# 9DofImu.net
KiCad netlist of a schematic drawn in EAGLE
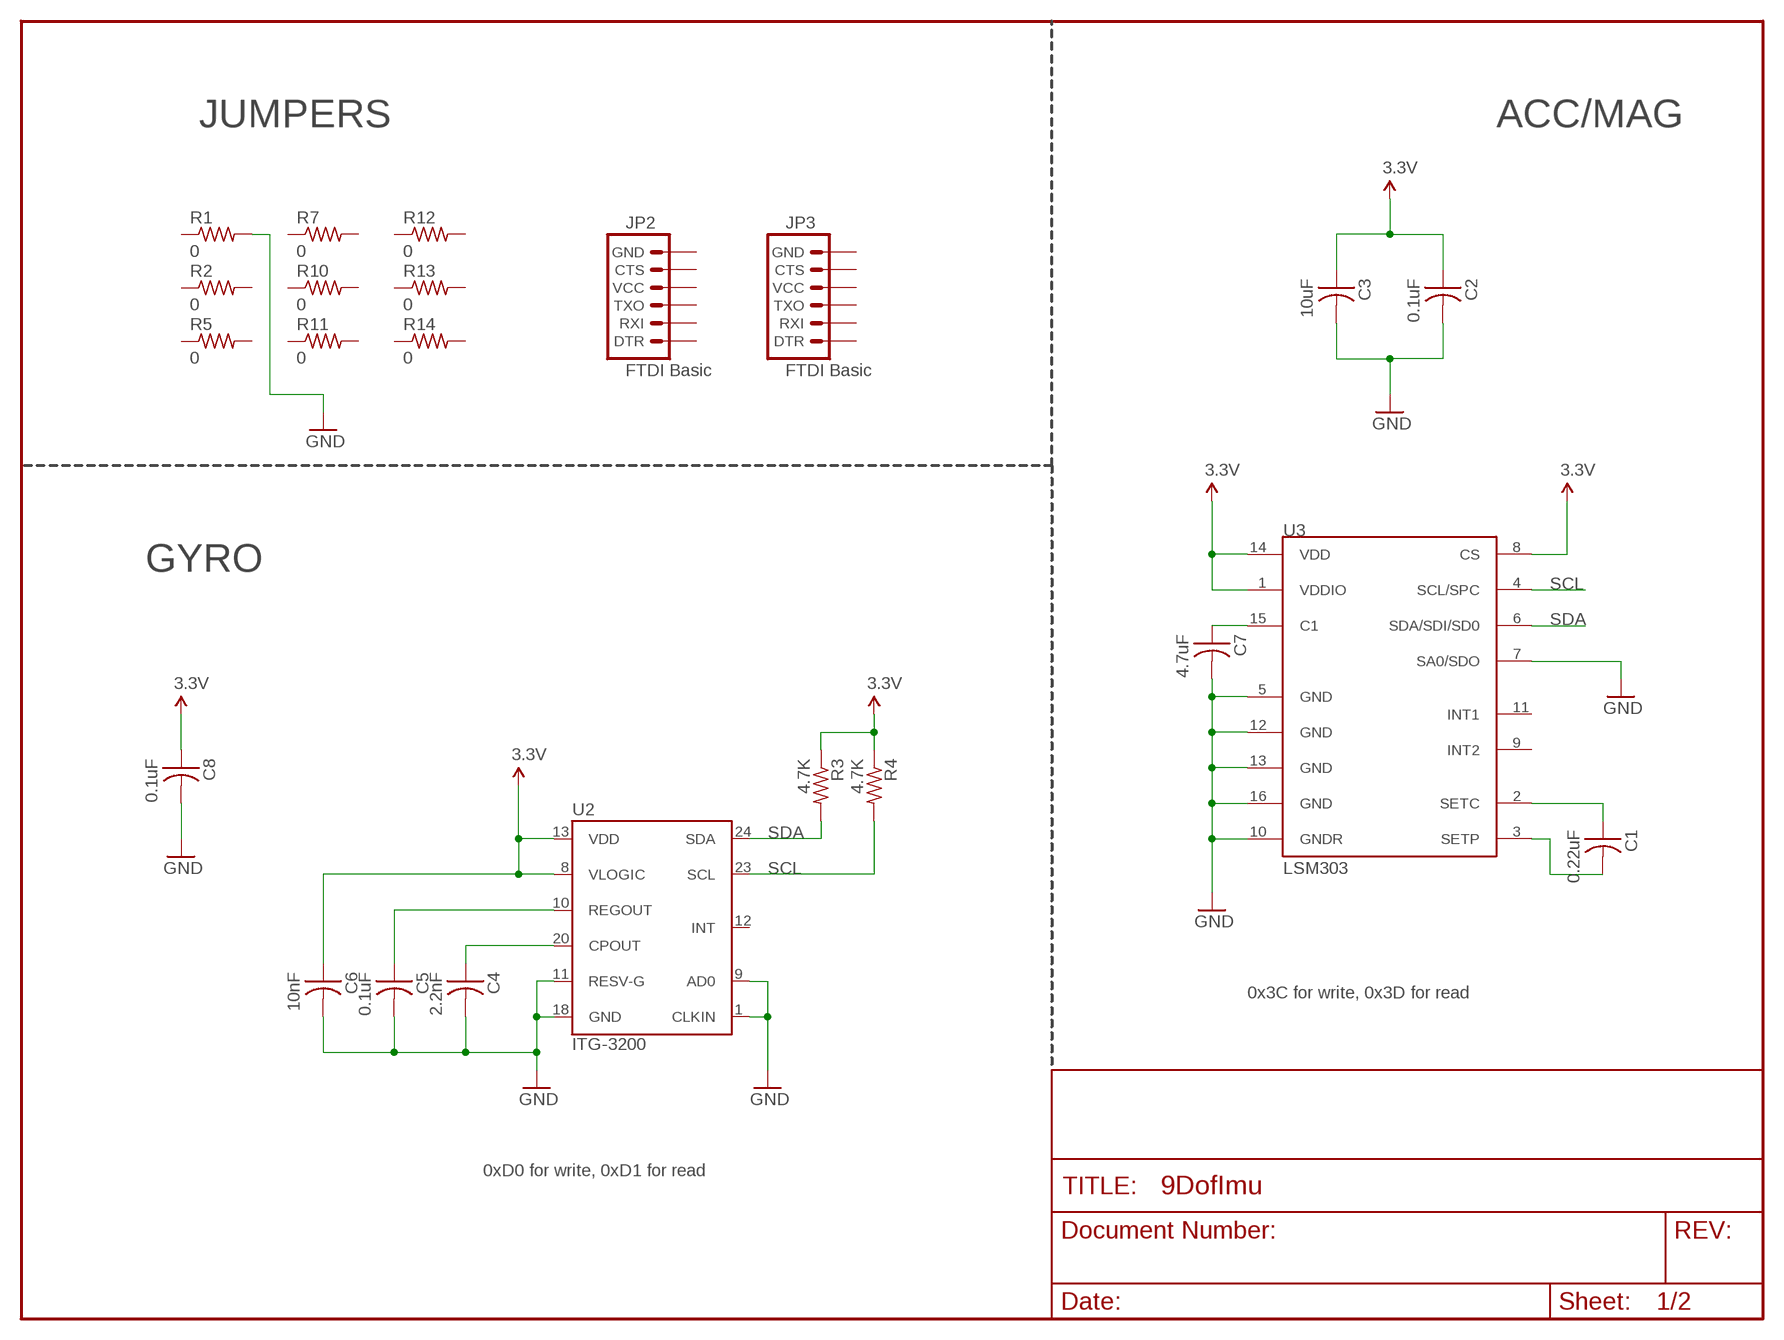
[diagram p0: schematic, sheet 1]
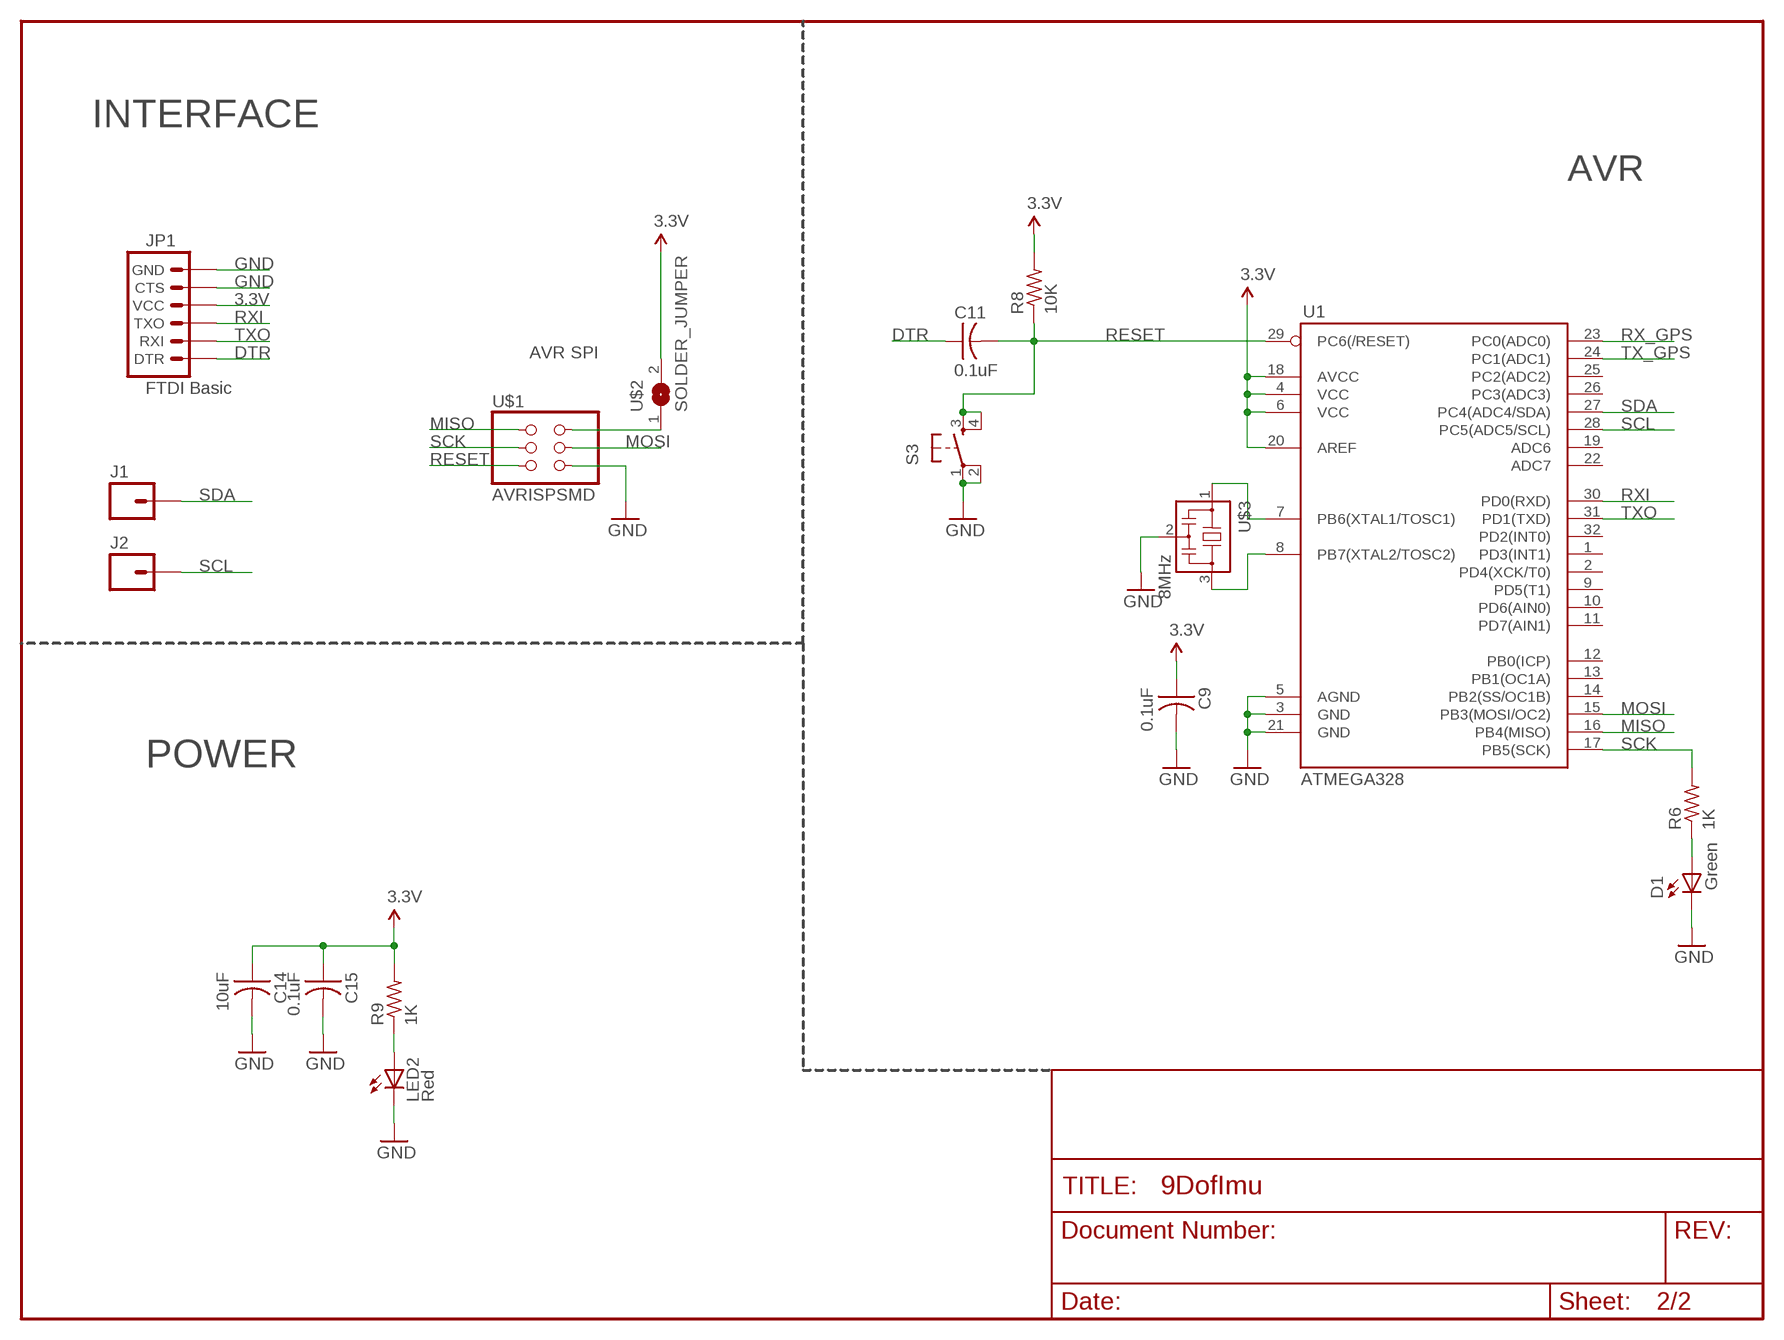
[diagram p1: schematic, sheet 2]

(export (version "E")
  (design (tool "Eeschema 10.0.6"))
  (components
    (comp (ref "C9")
      (value "0.1uF")
      (footprint "eagle-import:C1206")
      (libsource (lib "eagle-import") (part "CAP-US1206"))
    )
    (comp (ref "C11")
      (value "0.1uF")
      (footprint "eagle-import:C1206")
      (libsource (lib "eagle-import") (part "CAP-US1206"))
    )
    (comp (ref "C14")
      (value "10uF")
      (footprint "eagle-import:C1206")
      (libsource (lib "eagle-import") (part "CAP-US1206"))
    )
    (comp (ref "C15")
      (value "0.1uF")
      (footprint "eagle-import:C1206")
      (libsource (lib "eagle-import") (part "CAP-US1206"))
    )
    (comp (ref "D1")
      (value "Green")
      (footprint "eagle-import:LED-1206")
      (libsource (lib "eagle-import") (part "LED1206"))
    )
    (comp (ref "J1")
      (value "M01PTH")
      (footprint "eagle-import:1X01")
      (libsource (lib "eagle-import") (part "M01PTH"))
    )
    (comp (ref "J2")
      (value "M01PTH")
      (footprint "eagle-import:1X01")
      (libsource (lib "eagle-import") (part "M01PTH"))
    )
    (comp (ref "JP1")
      (value "FTDI Basic")
      (footprint "eagle-import:1X06-KIT")
      (libsource (lib "eagle-import") (part "ARDUINO_SERIAL_PROGRAMPTH-KIT"))
    )
    (comp (ref "LED2")
      (value "Red")
      (footprint "eagle-import:LED-1206")
      (libsource (lib "eagle-import") (part "LED1206"))
    )
    (comp (ref "R6")
      (value "1K")
      (footprint "eagle-import:R1206")
      (libsource (lib "eagle-import") (part "RES-US1206"))
    )
    (comp (ref "R8")
      (value "10K")
      (footprint "eagle-import:R1206")
      (libsource (lib "eagle-import") (part "RES-US1206"))
    )
    (comp (ref "R9")
      (value "1K")
      (footprint "eagle-import:R1206FAB")
      (libsource (lib "eagle-import") (part "RES-US1206FAB"))
    )
    (comp (ref "S3")
      (value "6MM_SWITCH6MM_SWITCH")
      (footprint "eagle-import:6MM_SWITCH")
      (libsource (lib "eagle-import") (part "6MM_SWITCH6MM_SWITCH"))
    )
    (comp (ref "U$1")
      (value "AVRISPSMD")
      (footprint "eagle-import:2X03SMD")
      (libsource (lib "eagle-import") (part "AVRISPSMD"))
    )
    (comp (ref "U$2")
      (value "SOLDER_JUMPER")
      (footprint "eagle-import:SJFAB")
      (libsource (lib "eagle-import") (part "SOLDER_JUMPER"))
    )
    (comp (ref "U$3")
      (value "8MHz")
      (footprint "eagle-import:EFOBM")
      (libsource (lib "eagle-import") (part "RESONATOR"))
    )
    (comp (ref "U1")
      (value "ATMEGA328")
      (footprint "eagle-import:TQFP32-08")
      (libsource (lib "eagle-import") (part "ATMEGA168"))
    )
    (comp (ref "C1")
      (value "0.22uF")
      (footprint "eagle-import:C1206")
      (libsource (lib "eagle-import") (part "CAP-US1206"))
    )
    (comp (ref "C2")
      (value "0.1uF")
      (footprint "eagle-import:C1206")
      (libsource (lib "eagle-import") (part "CAP-US1206"))
    )
    (comp (ref "C3")
      (value "10uF")
      (footprint "eagle-import:C1206")
      (libsource (lib "eagle-import") (part "CAP-US1206"))
    )
    (comp (ref "C4")
      (value "2.2nF")
      (footprint "eagle-import:C1206")
      (libsource (lib "eagle-import") (part "CAP-US1206"))
    )
    (comp (ref "C5")
      (value "0.1uF")
      (footprint "eagle-import:C1206")
      (libsource (lib "eagle-import") (part "CAP-US1206"))
    )
    (comp (ref "C6")
      (value "10nF")
      (footprint "eagle-import:C1206")
      (libsource (lib "eagle-import") (part "CAP-US1206"))
    )
    (comp (ref "C7")
      (value "4.7uF")
      (footprint "eagle-import:C1206")
      (libsource (lib "eagle-import") (part "CAP-US1206"))
    )
    (comp (ref "C8")
      (value "0.1uF")
      (footprint "eagle-import:C1206")
      (libsource (lib "eagle-import") (part "CAP-US1206"))
    )
    (comp (ref "JP2")
      (value "FTDI Basic")
      (footprint "eagle-import:1X06-KIT")
      (libsource (lib "eagle-import") (part "ARDUINO_SERIAL_PROGRAMPTH-KIT"))
    )
    (comp (ref "JP3")
      (value "FTDI Basic")
      (footprint "eagle-import:1X06-KIT")
      (libsource (lib "eagle-import") (part "ARDUINO_SERIAL_PROGRAMPTH-KIT"))
    )
    (comp (ref "R1")
      (value "0")
      (footprint "eagle-import:R1206FAB")
      (libsource (lib "eagle-import") (part "RES-US1206FAB"))
    )
    (comp (ref "R2")
      (value "0")
      (footprint "eagle-import:R1206FAB")
      (libsource (lib "eagle-import") (part "RES-US1206FAB"))
    )
    (comp (ref "R3")
      (value "4.7K")
      (footprint "eagle-import:R1206")
      (libsource (lib "eagle-import") (part "RES-US1206"))
    )
    (comp (ref "R4")
      (value "4.7K")
      (footprint "eagle-import:R1206FAB")
      (libsource (lib "eagle-import") (part "RES-US1206FAB"))
    )
    (comp (ref "R5")
      (value "0")
      (footprint "eagle-import:R1206FAB")
      (libsource (lib "eagle-import") (part "RES-US1206FAB"))
    )
    (comp (ref "R7")
      (value "0")
      (footprint "eagle-import:R1206FAB")
      (libsource (lib "eagle-import") (part "RES-US1206FAB"))
    )
    (comp (ref "R10")
      (value "0")
      (footprint "eagle-import:R1206FAB")
      (libsource (lib "eagle-import") (part "RES-US1206FAB"))
    )
    (comp (ref "R11")
      (value "0")
      (footprint "eagle-import:R1206FAB")
      (libsource (lib "eagle-import") (part "RES-US1206FAB"))
    )
    (comp (ref "R12")
      (value "0")
      (footprint "eagle-import:R1206FAB")
      (libsource (lib "eagle-import") (part "RES-US1206FAB"))
    )
    (comp (ref "R13")
      (value "0")
      (footprint "eagle-import:R1206FAB")
      (libsource (lib "eagle-import") (part "RES-US1206FAB"))
    )
    (comp (ref "R14")
      (value "0")
      (footprint "eagle-import:R1206FAB")
      (libsource (lib "eagle-import") (part "RES-US1206FAB"))
    )
    (comp (ref "U2")
      (value "ITG-3200")
      (footprint "eagle-import:QFN-24")
      (libsource (lib "eagle-import") (part "ITG-3200"))
    )
    (comp (ref "U3")
      (value "LSM303")
      (footprint "eagle-import:LGA16-3MM")
      (libsource (lib "eagle-import") (part "LSM303"))
    )
  )
  (nets
    (net (code "1") (name "3.3V") (class "Default")
      (node (ref "C14") (pin "1") (pinfunction "1_1") (pintype "passive"))
      (node (ref "C15") (pin "1") (pinfunction "1_1") (pintype "passive"))
      (node (ref "C2") (pin "1") (pinfunction "1_1") (pintype "passive"))
      (node (ref "C3") (pin "1") (pinfunction "1_1") (pintype "passive"))
      (node (ref "C6") (pin "1") (pinfunction "1_1") (pintype "passive"))
      (node (ref "C8") (pin "1") (pinfunction "1_1") (pintype "passive"))
      (node (ref "C9") (pin "1") (pinfunction "1_1") (pintype "passive"))
      (node (ref "JP1") (pin "4") (pinfunction "VCC_4") (pintype "passive"))
      (node (ref "R3") (pin "1") (pinfunction "1_1") (pintype "passive"))
      (node (ref "R4") (pin "1") (pinfunction "1_1") (pintype "passive"))
      (node (ref "R8") (pin "2") (pinfunction "2_2") (pintype "passive"))
      (node (ref "R9") (pin "2") (pinfunction "2_2") (pintype "passive"))
      (node (ref "U$2") (pin "2") (pinfunction "2_2") (pintype "passive"))
      (node (ref "U1") (pin "18") (pinfunction "AVCC_18") (pintype "bidirectional"))
      (node (ref "U1") (pin "20") (pinfunction "AREF_20") (pintype "bidirectional"))
      (node (ref "U1") (pin "4") (pinfunction "VCC_4") (pintype "bidirectional"))
      (node (ref "U1") (pin "6") (pinfunction "VCC_6") (pintype "bidirectional"))
      (node (ref "U2") (pin "13") (pinfunction "VDD_13") (pintype "bidirectional"))
      (node (ref "U2") (pin "8") (pinfunction "VLOGIC_8") (pintype "bidirectional"))
      (node (ref "U3") (pin "1") (pinfunction "VDDIO_1") (pintype "bidirectional"))
      (node (ref "U3") (pin "14") (pinfunction "VDD_14") (pintype "bidirectional"))
      (node (ref "U3") (pin "8") (pinfunction "CS_8") (pintype "bidirectional"))
    )
    (net (code "2") (name "DTR") (class "Default")
      (node (ref "C11") (pin "1") (pinfunction "1_1") (pintype "passive"))
      (node (ref "JP1") (pin "1") (pinfunction "DTR_1") (pintype "passive"))
    )
    (net (code "3") (name "GND") (class "Default")
      (node (ref "C14") (pin "2") (pinfunction "2_2") (pintype "passive"))
      (node (ref "C15") (pin "2") (pinfunction "2_2") (pintype "passive"))
      (node (ref "C2") (pin "2") (pinfunction "2_2") (pintype "passive"))
      (node (ref "C3") (pin "2") (pinfunction "2_2") (pintype "passive"))
      (node (ref "C4") (pin "2") (pinfunction "2_2") (pintype "passive"))
      (node (ref "C5") (pin "2") (pinfunction "2_2") (pintype "passive"))
      (node (ref "C6") (pin "2") (pinfunction "2_2") (pintype "passive"))
      (node (ref "C7") (pin "2") (pinfunction "2_2") (pintype "passive"))
      (node (ref "C8") (pin "2") (pinfunction "2_2") (pintype "passive"))
      (node (ref "C9") (pin "2") (pinfunction "2_2") (pintype "passive"))
      (node (ref "D1") (pin "C") (pinfunction "C_C") (pintype "passive"))
      (node (ref "JP1") (pin "5") (pinfunction "CTS_5") (pintype "passive"))
      (node (ref "JP1") (pin "6") (pinfunction "GND_6") (pintype "passive"))
      (node (ref "LED2") (pin "C") (pinfunction "C_C") (pintype "passive"))
      (node (ref "R1") (pin "2") (pinfunction "2_2") (pintype "passive"))
      (node (ref "S3") (pin "1") (pinfunction "P_1") (pintype "passive"))
      (node (ref "S3") (pin "2") (pinfunction "P1_2") (pintype "passive"))
      (node (ref "U$1") (pin "6") (pinfunction "GND_6") (pintype "passive"))
      (node (ref "U$3") (pin "2") (pinfunction "2_2") (pintype "passive"))
      (node (ref "U1") (pin "21") (pinfunction "GND_21") (pintype "bidirectional"))
      (node (ref "U1") (pin "3") (pinfunction "GND_3") (pintype "bidirectional"))
      (node (ref "U1") (pin "5") (pinfunction "AGND_5") (pintype "bidirectional"))
      (node (ref "U2") (pin "1") (pinfunction "CLKIN_1") (pintype "bidirectional"))
      (node (ref "U2") (pin "11") (pinfunction "RESV-G_11") (pintype "bidirectional"))
      (node (ref "U2") (pin "18") (pinfunction "GND_18") (pintype "bidirectional"))
      (node (ref "U2") (pin "9") (pinfunction "AD0_9") (pintype "bidirectional"))
      (node (ref "U3") (pin "10") (pinfunction "GNDR_10") (pintype "bidirectional"))
      (node (ref "U3") (pin "12") (pinfunction "GND_12") (pintype "bidirectional"))
      (node (ref "U3") (pin "13") (pinfunction "GND_13") (pintype "bidirectional"))
      (node (ref "U3") (pin "16") (pinfunction "GND_16") (pintype "bidirectional"))
      (node (ref "U3") (pin "5") (pinfunction "GND_5") (pintype "bidirectional"))
      (node (ref "U3") (pin "7") (pinfunction "SA0/SDO_7") (pintype "bidirectional"))
    )
    (net (code "4") (name "MISO") (class "Default")
      (node (ref "U$1") (pin "1") (pinfunction "MISO_1") (pintype "passive"))
      (node (ref "U1") (pin "16") (pinfunction "PB4(MISO)_16") (pintype "bidirectional"))
    )
    (net (code "5") (name "MOSI") (class "Default")
      (node (ref "U$1") (pin "4") (pinfunction "MOSI_4") (pintype "passive"))
      (node (ref "U1") (pin "15") (pinfunction "PB3(MOSI/OC2)_15") (pintype "bidirectional"))
    )
    (net (code "6") (name "Net-(D1-PadA)") (class "Default")
      (node (ref "D1") (pin "A") (pinfunction "A_A") (pintype "passive"))
      (node (ref "R6") (pin "1") (pinfunction "1_1") (pintype "passive"))
    )
    (net (code "7") (name "Net-(LED2-PadA)") (class "Default")
      (node (ref "LED2") (pin "A") (pinfunction "A_A") (pintype "passive"))
      (node (ref "R9") (pin "1") (pinfunction "1_1") (pintype "passive"))
    )
    (net (code "8") (name "Net-(U$1-VCC)") (class "Default")
      (node (ref "U$1") (pin "2") (pinfunction "VCC_2") (pintype "passive"))
      (node (ref "U$2") (pin "1") (pinfunction "1_1") (pintype "passive"))
    )
    (net (code "9") (name "Net-(U1-PB6(XTAL1{slash}TOSC1))") (class "Default")
      (node (ref "U$3") (pin "1") (pinfunction "1_1") (pintype "passive"))
      (node (ref "U1") (pin "7") (pinfunction "PB6(XTAL1/TOSC1)_7") (pintype "bidirectional"))
    )
    (net (code "10") (name "Net-(U1-PB7(XTAL2{slash}TOSC2))") (class "Default")
      (node (ref "U$3") (pin "3") (pinfunction "3_3") (pintype "passive"))
      (node (ref "U1") (pin "8") (pinfunction "PB7(XTAL2/TOSC2)_8") (pintype "bidirectional"))
    )
    (net (code "11") (name "Net-(U2-CPOUT)") (class "Default")
      (node (ref "C4") (pin "1") (pinfunction "1_1") (pintype "passive"))
      (node (ref "U2") (pin "20") (pinfunction "CPOUT_20") (pintype "bidirectional"))
    )
    (net (code "12") (name "Net-(U2-REGOUT)") (class "Default")
      (node (ref "C5") (pin "1") (pinfunction "1_1") (pintype "passive"))
      (node (ref "U2") (pin "10") (pinfunction "REGOUT_10") (pintype "bidirectional"))
    )
    (net (code "13") (name "Net-(U3-C1)") (class "Default")
      (node (ref "C7") (pin "1") (pinfunction "1_1") (pintype "passive"))
      (node (ref "U3") (pin "15") (pinfunction "C1_15") (pintype "bidirectional"))
    )
    (net (code "14") (name "Net-(U3-SETC)") (class "Default")
      (node (ref "C1") (pin "1") (pinfunction "1_1") (pintype "passive"))
      (node (ref "U3") (pin "2") (pinfunction "SETC_2") (pintype "bidirectional"))
    )
    (net (code "15") (name "Net-(U3-SETP)") (class "Default")
      (node (ref "C1") (pin "2") (pinfunction "2_2") (pintype "passive"))
      (node (ref "U3") (pin "3") (pinfunction "SETP_3") (pintype "bidirectional"))
    )
    (net (code "16") (name "RESET") (class "Default")
      (node (ref "C11") (pin "2") (pinfunction "2_2") (pintype "passive"))
      (node (ref "R8") (pin "1") (pinfunction "1_1") (pintype "passive"))
      (node (ref "S3") (pin "3") (pinfunction "S_3") (pintype "passive"))
      (node (ref "S3") (pin "4") (pinfunction "S1_4") (pintype "passive"))
      (node (ref "U$1") (pin "5") (pinfunction "RST_5") (pintype "passive"))
      (node (ref "U1") (pin "29") (pinfunction "PC6(/RESET)_29") (pintype "bidirectional"))
    )
    (net (code "17") (name "RXI") (class "Default")
      (node (ref "JP1") (pin "3") (pinfunction "TXO_3") (pintype "passive"))
      (node (ref "U1") (pin "30") (pinfunction "PD0(RXD)_30") (pintype "bidirectional"))
    )
    (net (code "18") (name "RX_GPS") (class "Default")
      (node (ref "U1") (pin "23") (pinfunction "PC0(ADC0)_23") (pintype "bidirectional"))
    )
    (net (code "19") (name "SCK") (class "Default")
      (node (ref "R6") (pin "2") (pinfunction "2_2") (pintype "passive"))
      (node (ref "U$1") (pin "3") (pinfunction "SCK_3") (pintype "passive"))
      (node (ref "U1") (pin "17") (pinfunction "PB5(SCK)_17") (pintype "bidirectional"))
    )
    (net (code "20") (name "SCL") (class "Default")
      (node (ref "J2") (pin "1") (pinfunction "1_1") (pintype "passive"))
      (node (ref "R4") (pin "2") (pinfunction "2_2") (pintype "passive"))
      (node (ref "U1") (pin "28") (pinfunction "PC5(ADC5/SCL)_28") (pintype "bidirectional"))
      (node (ref "U2") (pin "23") (pinfunction "SCL_23") (pintype "bidirectional"))
      (node (ref "U3") (pin "4") (pinfunction "SCL/SPC_4") (pintype "bidirectional"))
    )
    (net (code "21") (name "SDA") (class "Default")
      (node (ref "J1") (pin "1") (pinfunction "1_1") (pintype "passive"))
      (node (ref "R3") (pin "2") (pinfunction "2_2") (pintype "passive"))
      (node (ref "U1") (pin "27") (pinfunction "PC4(ADC4/SDA)_27") (pintype "bidirectional"))
      (node (ref "U2") (pin "24") (pinfunction "SDA_24") (pintype "bidirectional"))
      (node (ref "U3") (pin "6") (pinfunction "SDA/SDI/SD0_6") (pintype "bidirectional"))
    )
    (net (code "22") (name "TXO") (class "Default")
      (node (ref "JP1") (pin "2") (pinfunction "RXI_2") (pintype "passive"))
      (node (ref "U1") (pin "31") (pinfunction "PD1(TXD)_31") (pintype "bidirectional"))
    )
    (net (code "23") (name "TX_GPS") (class "Default")
      (node (ref "U1") (pin "24") (pinfunction "PC1(ADC1)_24") (pintype "bidirectional"))
    )
    (net (code "24") (name "unconnected-(JP2-CTS-Pad5)") (class "Default")
      (node (ref "JP2") (pin "5") (pinfunction "CTS_5") (pintype "passive"))
    )
    (net (code "25") (name "unconnected-(JP2-DTR-Pad1)") (class "Default")
      (node (ref "JP2") (pin "1") (pinfunction "DTR_1") (pintype "passive"))
    )
    (net (code "26") (name "unconnected-(JP2-GND-Pad6)") (class "Default")
      (node (ref "JP2") (pin "6") (pinfunction "GND_6") (pintype "passive"))
    )
    (net (code "27") (name "unconnected-(JP2-RXI-Pad2)") (class "Default")
      (node (ref "JP2") (pin "2") (pinfunction "RXI_2") (pintype "passive"))
    )
    (net (code "28") (name "unconnected-(JP2-TXO-Pad3)") (class "Default")
      (node (ref "JP2") (pin "3") (pinfunction "TXO_3") (pintype "passive"))
    )
    (net (code "29") (name "unconnected-(JP2-VCC-Pad4)") (class "Default")
      (node (ref "JP2") (pin "4") (pinfunction "VCC_4") (pintype "passive"))
    )
    (net (code "30") (name "unconnected-(JP3-CTS-Pad5)") (class "Default")
      (node (ref "JP3") (pin "5") (pinfunction "CTS_5") (pintype "passive"))
    )
    (net (code "31") (name "unconnected-(JP3-DTR-Pad1)") (class "Default")
      (node (ref "JP3") (pin "1") (pinfunction "DTR_1") (pintype "passive"))
    )
    (net (code "32") (name "unconnected-(JP3-GND-Pad6)") (class "Default")
      (node (ref "JP3") (pin "6") (pinfunction "GND_6") (pintype "passive"))
    )
    (net (code "33") (name "unconnected-(JP3-RXI-Pad2)") (class "Default")
      (node (ref "JP3") (pin "2") (pinfunction "RXI_2") (pintype "passive"))
    )
    (net (code "34") (name "unconnected-(JP3-TXO-Pad3)") (class "Default")
      (node (ref "JP3") (pin "3") (pinfunction "TXO_3") (pintype "passive"))
    )
    (net (code "35") (name "unconnected-(JP3-VCC-Pad4)") (class "Default")
      (node (ref "JP3") (pin "4") (pinfunction "VCC_4") (pintype "passive"))
    )
    (net (code "36") (name "unconnected-(R1-Pad1)") (class "Default")
      (node (ref "R1") (pin "1") (pinfunction "1_1") (pintype "passive"))
    )
    (net (code "37") (name "unconnected-(R2-Pad1)") (class "Default")
      (node (ref "R2") (pin "1") (pinfunction "1_1") (pintype "passive"))
    )
    (net (code "38") (name "unconnected-(R2-Pad2)") (class "Default")
      (node (ref "R2") (pin "2") (pinfunction "2_2") (pintype "passive"))
    )
    (net (code "39") (name "unconnected-(R5-Pad1)") (class "Default")
      (node (ref "R5") (pin "1") (pinfunction "1_1") (pintype "passive"))
    )
    (net (code "40") (name "unconnected-(R5-Pad2)") (class "Default")
      (node (ref "R5") (pin "2") (pinfunction "2_2") (pintype "passive"))
    )
    (net (code "41") (name "unconnected-(R7-Pad1)") (class "Default")
      (node (ref "R7") (pin "1") (pinfunction "1_1") (pintype "passive"))
    )
    (net (code "42") (name "unconnected-(R7-Pad2)") (class "Default")
      (node (ref "R7") (pin "2") (pinfunction "2_2") (pintype "passive"))
    )
    (net (code "43") (name "unconnected-(R10-Pad1)") (class "Default")
      (node (ref "R10") (pin "1") (pinfunction "1_1") (pintype "passive"))
    )
    (net (code "44") (name "unconnected-(R10-Pad2)") (class "Default")
      (node (ref "R10") (pin "2") (pinfunction "2_2") (pintype "passive"))
    )
    (net (code "45") (name "unconnected-(R11-Pad1)") (class "Default")
      (node (ref "R11") (pin "1") (pinfunction "1_1") (pintype "passive"))
    )
    (net (code "46") (name "unconnected-(R11-Pad2)") (class "Default")
      (node (ref "R11") (pin "2") (pinfunction "2_2") (pintype "passive"))
    )
    (net (code "47") (name "unconnected-(R12-Pad1)") (class "Default")
      (node (ref "R12") (pin "1") (pinfunction "1_1") (pintype "passive"))
    )
    (net (code "48") (name "unconnected-(R12-Pad2)") (class "Default")
      (node (ref "R12") (pin "2") (pinfunction "2_2") (pintype "passive"))
    )
    (net (code "49") (name "unconnected-(R13-Pad1)") (class "Default")
      (node (ref "R13") (pin "1") (pinfunction "1_1") (pintype "passive"))
    )
    (net (code "50") (name "unconnected-(R13-Pad2)") (class "Default")
      (node (ref "R13") (pin "2") (pinfunction "2_2") (pintype "passive"))
    )
    (net (code "51") (name "unconnected-(R14-Pad1)") (class "Default")
      (node (ref "R14") (pin "1") (pinfunction "1_1") (pintype "passive"))
    )
    (net (code "52") (name "unconnected-(R14-Pad2)") (class "Default")
      (node (ref "R14") (pin "2") (pinfunction "2_2") (pintype "passive"))
    )
    (net (code "53") (name "unconnected-(U1-ADC6-Pad19)") (class "Default")
      (node (ref "U1") (pin "19") (pinfunction "ADC6_19") (pintype "bidirectional"))
    )
    (net (code "54") (name "unconnected-(U1-ADC7-Pad22)") (class "Default")
      (node (ref "U1") (pin "22") (pinfunction "ADC7_22") (pintype "bidirectional"))
    )
    (net (code "55") (name "unconnected-(U1-PB0(ICP)-Pad12)") (class "Default")
      (node (ref "U1") (pin "12") (pinfunction "PB0(ICP)_12") (pintype "bidirectional"))
    )
    (net (code "56") (name "unconnected-(U1-PB1(OC1A)-Pad13)") (class "Default")
      (node (ref "U1") (pin "13") (pinfunction "PB1(OC1A)_13") (pintype "bidirectional"))
    )
    (net (code "57") (name "unconnected-(U1-PB2(SS{slash}OC1B)-Pad14)") (class "Default")
      (node (ref "U1") (pin "14") (pinfunction "PB2(SS/OC1B)_14") (pintype "bidirectional"))
    )
    (net (code "58") (name "unconnected-(U1-PC2(ADC2)-Pad25)") (class "Default")
      (node (ref "U1") (pin "25") (pinfunction "PC2(ADC2)_25") (pintype "bidirectional"))
    )
    (net (code "59") (name "unconnected-(U1-PC3(ADC3)-Pad26)") (class "Default")
      (node (ref "U1") (pin "26") (pinfunction "PC3(ADC3)_26") (pintype "bidirectional"))
    )
    (net (code "60") (name "unconnected-(U1-PD2(INT0)-Pad32)") (class "Default")
      (node (ref "U1") (pin "32") (pinfunction "PD2(INT0)_32") (pintype "bidirectional"))
    )
    (net (code "61") (name "unconnected-(U1-PD3(INT1)-Pad1)") (class "Default")
      (node (ref "U1") (pin "1") (pinfunction "PD3(INT1)_1") (pintype "bidirectional"))
    )
    (net (code "62") (name "unconnected-(U1-PD4(XCK{slash}T0)-Pad2)") (class "Default")
      (node (ref "U1") (pin "2") (pinfunction "PD4(XCK/T0)_2") (pintype "bidirectional"))
    )
    (net (code "63") (name "unconnected-(U1-PD5(T1)-Pad9)") (class "Default")
      (node (ref "U1") (pin "9") (pinfunction "PD5(T1)_9") (pintype "bidirectional"))
    )
    (net (code "64") (name "unconnected-(U1-PD6(AIN0)-Pad10)") (class "Default")
      (node (ref "U1") (pin "10") (pinfunction "PD6(AIN0)_10") (pintype "bidirectional"))
    )
    (net (code "65") (name "unconnected-(U1-PD7(AIN1)-Pad11)") (class "Default")
      (node (ref "U1") (pin "11") (pinfunction "PD7(AIN1)_11") (pintype "bidirectional"))
    )
    (net (code "66") (name "unconnected-(U2-INT-Pad12)") (class "Default")
      (node (ref "U2") (pin "12") (pinfunction "INT_12") (pintype "bidirectional"))
    )
    (net (code "67") (name "unconnected-(U3-INT1-Pad11)") (class "Default")
      (node (ref "U3") (pin "11") (pinfunction "INT1_11") (pintype "bidirectional"))
    )
    (net (code "68") (name "unconnected-(U3-INT2-Pad9)") (class "Default")
      (node (ref "U3") (pin "9") (pinfunction "INT2_9") (pintype "bidirectional"))
    )
  )
)
